# reg.net
KiCad netlist of a schematic drawn in EAGLE
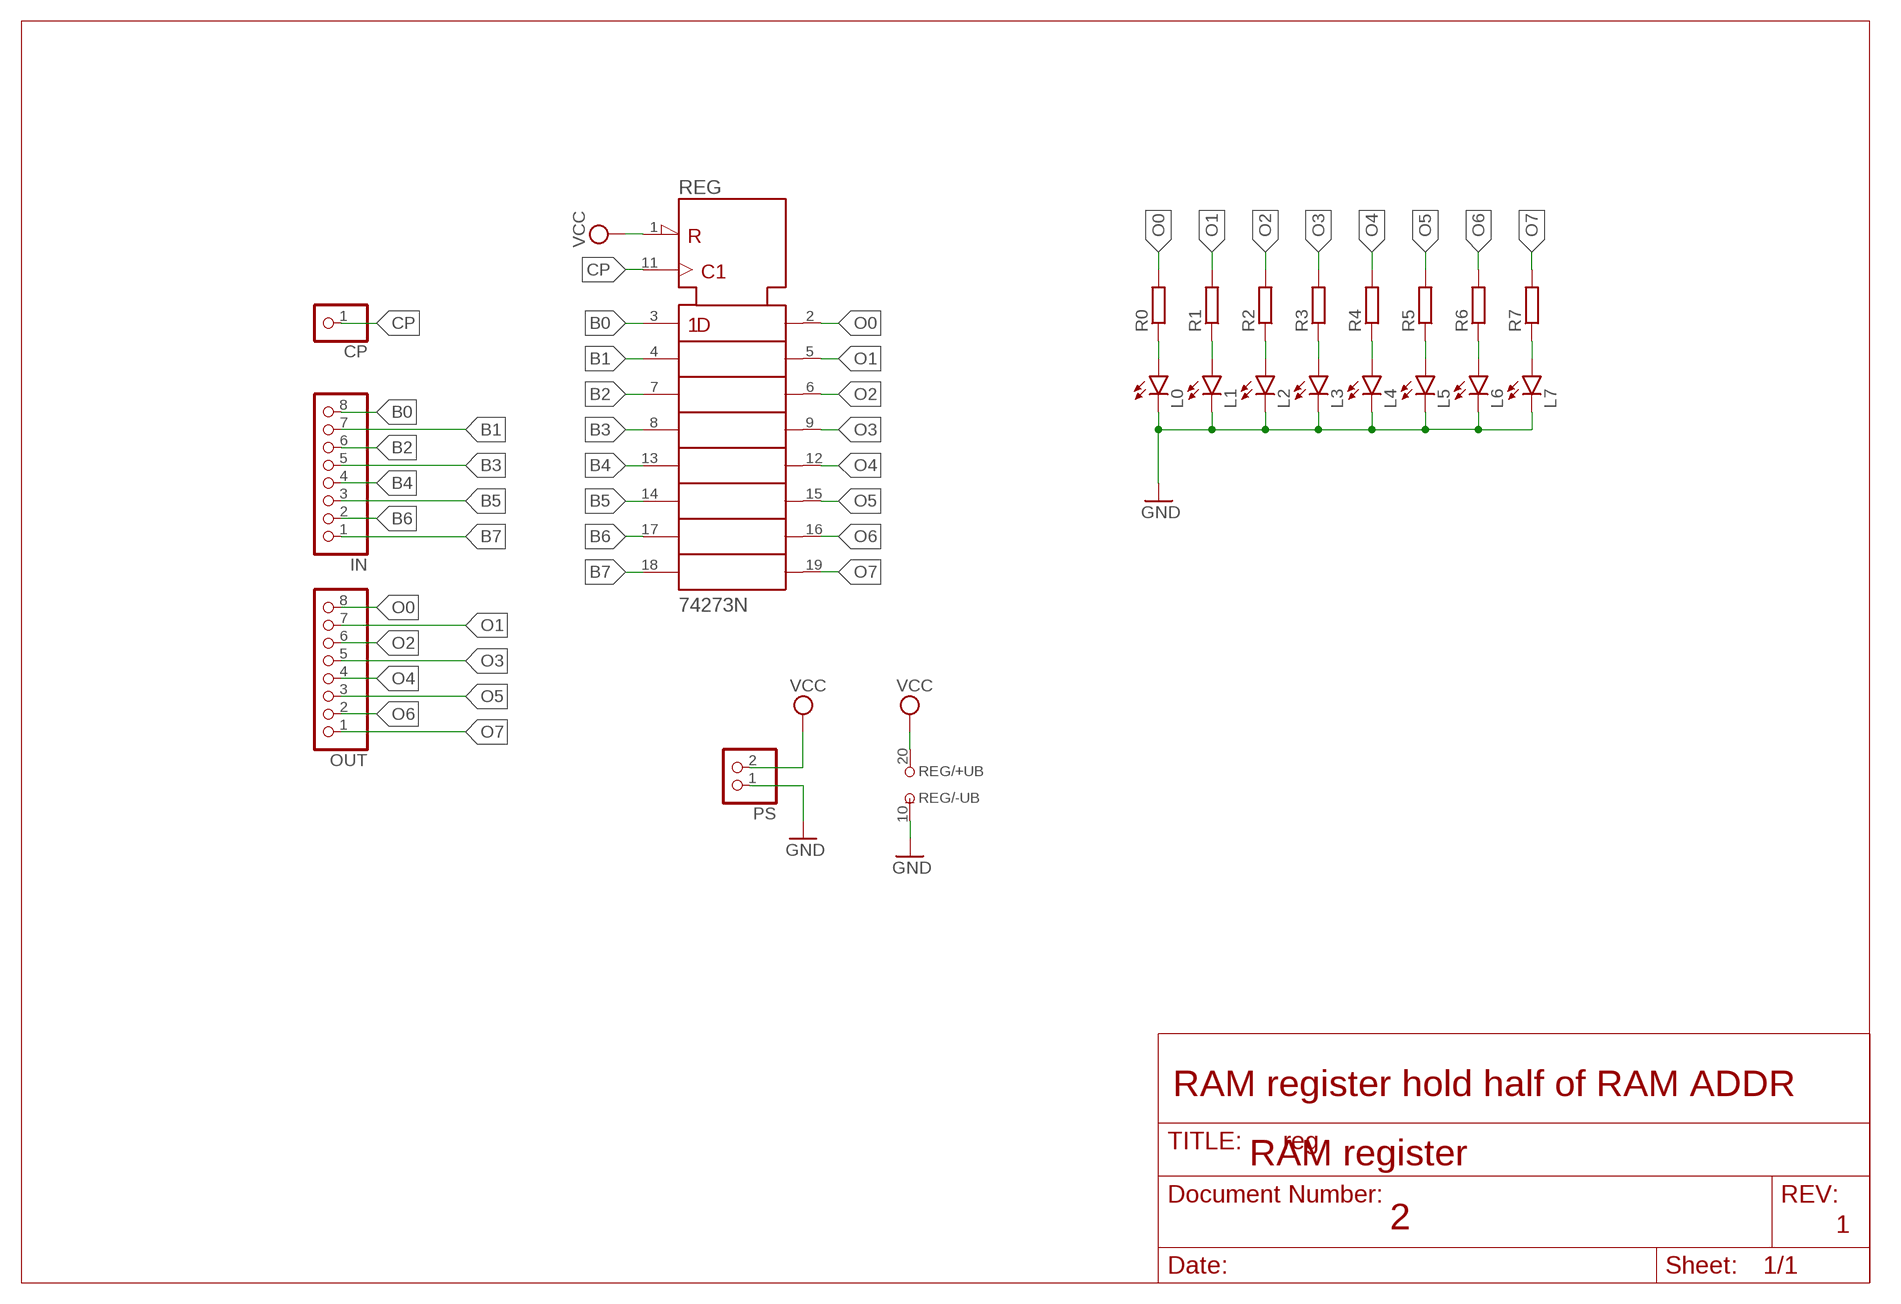
[diagram p0: schematic, sheet 1]

(export (version "E")
  (design (tool "Eeschema 10.0.6"))
  (components
    (comp (ref "CP")
      (value "PINHD-1X1")
      (footprint "eagle-import:1X01")
      (libsource (lib "eagle-import") (part "PINHD-1X1"))
    )
    (comp (ref "IN")
      (value "PINHD-1X8")
      (footprint "eagle-import:1X08")
      (libsource (lib "eagle-import") (part "PINHD-1X8"))
    )
    (comp (ref "L0")
      (value "LED5MM")
      (footprint "eagle-import:LED5MM")
      (libsource (lib "eagle-import") (part "LED5MM"))
    )
    (comp (ref "L1")
      (value "LED5MM")
      (footprint "eagle-import:LED5MM")
      (libsource (lib "eagle-import") (part "LED5MM"))
    )
    (comp (ref "L2")
      (value "LED5MM")
      (footprint "eagle-import:LED5MM")
      (libsource (lib "eagle-import") (part "LED5MM"))
    )
    (comp (ref "L3")
      (value "LED5MM")
      (footprint "eagle-import:LED5MM")
      (libsource (lib "eagle-import") (part "LED5MM"))
    )
    (comp (ref "L4")
      (value "LED5MM")
      (footprint "eagle-import:LED5MM")
      (libsource (lib "eagle-import") (part "LED5MM"))
    )
    (comp (ref "L5")
      (value "LED5MM")
      (footprint "eagle-import:LED5MM")
      (libsource (lib "eagle-import") (part "LED5MM"))
    )
    (comp (ref "L6")
      (value "LED5MM")
      (footprint "eagle-import:LED5MM")
      (libsource (lib "eagle-import") (part "LED5MM"))
    )
    (comp (ref "L7")
      (value "LED5MM")
      (footprint "eagle-import:LED5MM")
      (libsource (lib "eagle-import") (part "LED5MM"))
    )
    (comp (ref "OUT")
      (value "PINHD-1X8")
      (footprint "eagle-import:1X08")
      (libsource (lib "eagle-import") (part "PINHD-1X8"))
    )
    (comp (ref "PS")
      (value "PINHD-1X2")
      (footprint "eagle-import:1X02")
      (libsource (lib "eagle-import") (part "PINHD-1X2"))
    )
    (comp (ref "R0")
      (value "R-EU_0204/7")
      (footprint "eagle-import:0204_7")
      (libsource (lib "eagle-import") (part "R-EU_0204/7"))
    )
    (comp (ref "R1")
      (value "R-EU_0204/7")
      (footprint "eagle-import:0204_7")
      (libsource (lib "eagle-import") (part "R-EU_0204/7"))
    )
    (comp (ref "R2")
      (value "R-EU_0204/7")
      (footprint "eagle-import:0204_7")
      (libsource (lib "eagle-import") (part "R-EU_0204/7"))
    )
    (comp (ref "R3")
      (value "R-EU_0204/7")
      (footprint "eagle-import:0204_7")
      (libsource (lib "eagle-import") (part "R-EU_0204/7"))
    )
    (comp (ref "R4")
      (value "R-EU_0204/7")
      (footprint "eagle-import:0204_7")
      (libsource (lib "eagle-import") (part "R-EU_0204/7"))
    )
    (comp (ref "R5")
      (value "R-EU_0204/7")
      (footprint "eagle-import:0204_7")
      (libsource (lib "eagle-import") (part "R-EU_0204/7"))
    )
    (comp (ref "R6")
      (value "R-EU_0204/7")
      (footprint "eagle-import:0204_7")
      (libsource (lib "eagle-import") (part "R-EU_0204/7"))
    )
    (comp (ref "R7")
      (value "R-EU_0204/7")
      (footprint "eagle-import:0204_7")
      (libsource (lib "eagle-import") (part "R-EU_0204/7"))
    )
    (comp (ref "REG")
      (value "74273N")
      (footprint "eagle-import:DIL20")
      (libsource (lib "eagle-import") (part "74273N"))
    )
  )
  (nets
    (net (code "1") (name "B0") (class "Default")
      (node (ref "IN") (pin "8") (pinfunction "8_8") (pintype "passive"))
      (node (ref "REG") (pin "3") (pinfunction "1D_3") (pintype "input"))
    )
    (net (code "2") (name "B1") (class "Default")
      (node (ref "IN") (pin "7") (pinfunction "7_7") (pintype "passive"))
      (node (ref "REG") (pin "4") (pinfunction "2D_4") (pintype "input"))
    )
    (net (code "3") (name "B2") (class "Default")
      (node (ref "IN") (pin "6") (pinfunction "6_6") (pintype "passive"))
      (node (ref "REG") (pin "7") (pinfunction "3D_7") (pintype "input"))
    )
    (net (code "4") (name "B3") (class "Default")
      (node (ref "IN") (pin "5") (pinfunction "5_5") (pintype "passive"))
      (node (ref "REG") (pin "8") (pinfunction "4D_8") (pintype "input"))
    )
    (net (code "5") (name "B4") (class "Default")
      (node (ref "IN") (pin "4") (pinfunction "4_4") (pintype "passive"))
      (node (ref "REG") (pin "13") (pinfunction "5D_13") (pintype "input"))
    )
    (net (code "6") (name "B5") (class "Default")
      (node (ref "IN") (pin "3") (pinfunction "3_3") (pintype "passive"))
      (node (ref "REG") (pin "14") (pinfunction "6D_14") (pintype "input"))
    )
    (net (code "7") (name "B6") (class "Default")
      (node (ref "IN") (pin "2") (pinfunction "2_2") (pintype "passive"))
      (node (ref "REG") (pin "17") (pinfunction "7D_17") (pintype "input"))
    )
    (net (code "8") (name "B7") (class "Default")
      (node (ref "IN") (pin "1") (pinfunction "1_1") (pintype "passive"))
      (node (ref "REG") (pin "18") (pinfunction "8D_18") (pintype "input"))
    )
    (net (code "9") (name "CP") (class "Default")
      (node (ref "CP") (pin "1") (pinfunction "1_1") (pintype "passive"))
      (node (ref "REG") (pin "11") (pinfunction "CLK_11") (pintype "input"))
    )
    (net (code "10") (name "GND") (class "Default")
      (node (ref "L0") (pin "K") (pinfunction "C_K") (pintype "passive"))
      (node (ref "L1") (pin "K") (pinfunction "C_K") (pintype "passive"))
      (node (ref "L2") (pin "K") (pinfunction "C_K") (pintype "passive"))
      (node (ref "L3") (pin "K") (pinfunction "C_K") (pintype "passive"))
      (node (ref "L4") (pin "K") (pinfunction "C_K") (pintype "passive"))
      (node (ref "L5") (pin "K") (pinfunction "C_K") (pintype "passive"))
      (node (ref "L6") (pin "K") (pinfunction "C_K") (pintype "passive"))
      (node (ref "L7") (pin "K") (pinfunction "C_K") (pintype "passive"))
      (node (ref "PS") (pin "1") (pinfunction "1_1") (pintype "passive"))
      (node (ref "REG") (pin "10") (pinfunction "-UB_10") (pintype "power_in"))
    )
    (net (code "11") (name "Net-(L0-PadA)") (class "Default")
      (node (ref "L0") (pin "A") (pinfunction "A_A") (pintype "passive"))
      (node (ref "R0") (pin "1") (pinfunction "1_1") (pintype "passive"))
    )
    (net (code "12") (name "Net-(L1-PadA)") (class "Default")
      (node (ref "L1") (pin "A") (pinfunction "A_A") (pintype "passive"))
      (node (ref "R1") (pin "1") (pinfunction "1_1") (pintype "passive"))
    )
    (net (code "13") (name "Net-(L2-PadA)") (class "Default")
      (node (ref "L2") (pin "A") (pinfunction "A_A") (pintype "passive"))
      (node (ref "R2") (pin "1") (pinfunction "1_1") (pintype "passive"))
    )
    (net (code "14") (name "Net-(L3-PadA)") (class "Default")
      (node (ref "L3") (pin "A") (pinfunction "A_A") (pintype "passive"))
      (node (ref "R3") (pin "1") (pinfunction "1_1") (pintype "passive"))
    )
    (net (code "15") (name "Net-(L4-PadA)") (class "Default")
      (node (ref "L4") (pin "A") (pinfunction "A_A") (pintype "passive"))
      (node (ref "R4") (pin "1") (pinfunction "1_1") (pintype "passive"))
    )
    (net (code "16") (name "Net-(L5-PadA)") (class "Default")
      (node (ref "L5") (pin "A") (pinfunction "A_A") (pintype "passive"))
      (node (ref "R5") (pin "1") (pinfunction "1_1") (pintype "passive"))
    )
    (net (code "17") (name "Net-(L6-PadA)") (class "Default")
      (node (ref "L6") (pin "A") (pinfunction "A_A") (pintype "passive"))
      (node (ref "R6") (pin "1") (pinfunction "1_1") (pintype "passive"))
    )
    (net (code "18") (name "Net-(L7-PadA)") (class "Default")
      (node (ref "L7") (pin "A") (pinfunction "A_A") (pintype "passive"))
      (node (ref "R7") (pin "1") (pinfunction "1_1") (pintype "passive"))
    )
    (net (code "19") (name "O0") (class "Default")
      (node (ref "OUT") (pin "8") (pinfunction "8_8") (pintype "passive"))
      (node (ref "R0") (pin "2") (pinfunction "2_2") (pintype "passive"))
      (node (ref "REG") (pin "2") (pinfunction "1Q_2") (pintype "output"))
    )
    (net (code "20") (name "O1") (class "Default")
      (node (ref "OUT") (pin "7") (pinfunction "7_7") (pintype "passive"))
      (node (ref "R1") (pin "2") (pinfunction "2_2") (pintype "passive"))
      (node (ref "REG") (pin "5") (pinfunction "2Q_5") (pintype "output"))
    )
    (net (code "21") (name "O2") (class "Default")
      (node (ref "OUT") (pin "6") (pinfunction "6_6") (pintype "passive"))
      (node (ref "R2") (pin "2") (pinfunction "2_2") (pintype "passive"))
      (node (ref "REG") (pin "6") (pinfunction "3Q_6") (pintype "output"))
    )
    (net (code "22") (name "O3") (class "Default")
      (node (ref "OUT") (pin "5") (pinfunction "5_5") (pintype "passive"))
      (node (ref "R3") (pin "2") (pinfunction "2_2") (pintype "passive"))
      (node (ref "REG") (pin "9") (pinfunction "4Q_9") (pintype "output"))
    )
    (net (code "23") (name "O4") (class "Default")
      (node (ref "OUT") (pin "4") (pinfunction "4_4") (pintype "passive"))
      (node (ref "R4") (pin "2") (pinfunction "2_2") (pintype "passive"))
      (node (ref "REG") (pin "12") (pinfunction "5Q_12") (pintype "output"))
    )
    (net (code "24") (name "O5") (class "Default")
      (node (ref "OUT") (pin "3") (pinfunction "3_3") (pintype "passive"))
      (node (ref "R5") (pin "2") (pinfunction "2_2") (pintype "passive"))
      (node (ref "REG") (pin "15") (pinfunction "6Q_15") (pintype "output"))
    )
    (net (code "25") (name "O6") (class "Default")
      (node (ref "OUT") (pin "2") (pinfunction "2_2") (pintype "passive"))
      (node (ref "R6") (pin "2") (pinfunction "2_2") (pintype "passive"))
      (node (ref "REG") (pin "16") (pinfunction "7Q_16") (pintype "output"))
    )
    (net (code "26") (name "O7") (class "Default")
      (node (ref "OUT") (pin "1") (pinfunction "1_1") (pintype "passive"))
      (node (ref "R7") (pin "2") (pinfunction "2_2") (pintype "passive"))
      (node (ref "REG") (pin "19") (pinfunction "8Q_19") (pintype "output"))
    )
    (net (code "27") (name "VCC") (class "Default")
      (node (ref "PS") (pin "2") (pinfunction "2_2") (pintype "passive"))
      (node (ref "REG") (pin "1") (pinfunction "~{CLR}_1") (pintype "input"))
      (node (ref "REG") (pin "20") (pinfunction "+UB_20") (pintype "power_in"))
    )
  )
)
